# SCH_Test_2024-06-17.net
KiCad netlist of a schematic drawn in EasyEDA
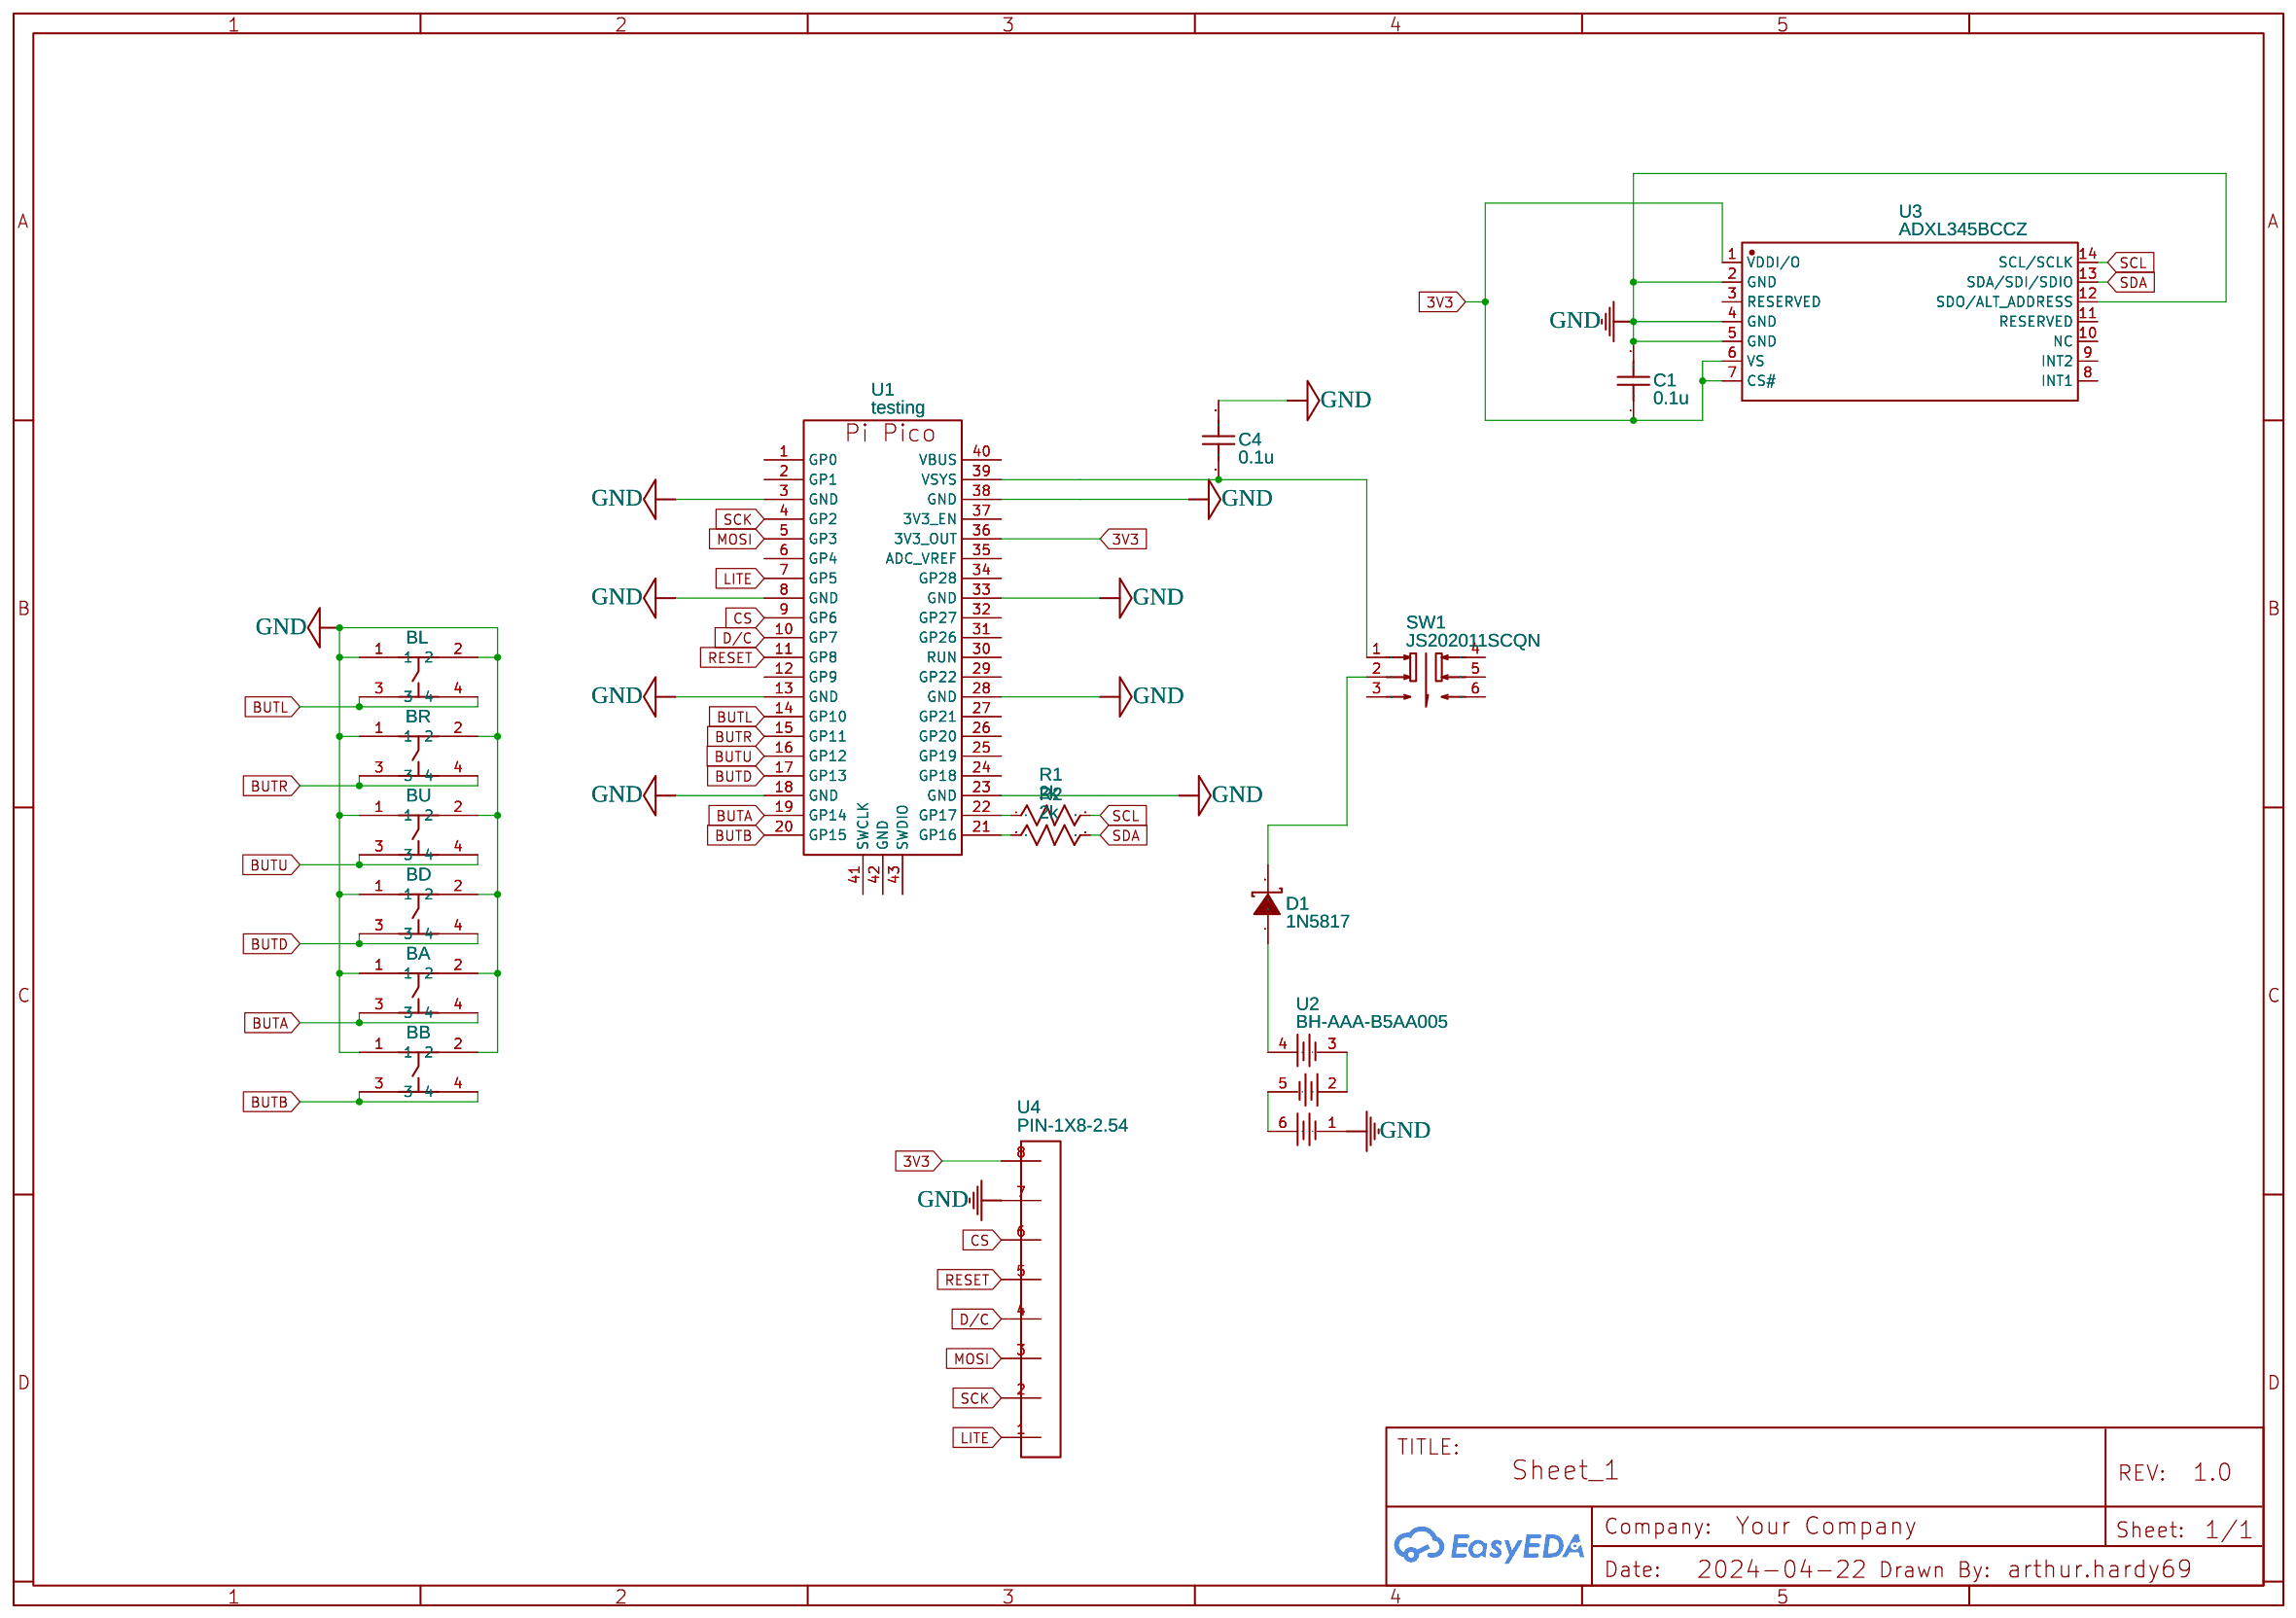
[diagram p0: schematic sheet]

(export (version "E")
  (design (tool "Eeschema 10.0.6"))
  (components
    (comp (ref "BA")
      (value "A")
      (fields (field (name "Manufacturer Part") "3101") (field (name "Manufacturer") "Adafruit"))
      (libsource (lib "") (part "Soft Tactile Button 8x8 (Adafruit 3101)"))
    )
    (comp (ref "BB")
      (value "B")
      (fields (field (name "Manufacturer Part") "3101") (field (name "Manufacturer") "Adafruit"))
      (libsource (lib "") (part "Soft Tactile Button 8x8 (Adafruit 3101)_1"))
    )
    (comp (ref "BD")
      (value "Down")
      (fields (field (name "Manufacturer Part") "3101") (field (name "Manufacturer") "Adafruit"))
      (libsource (lib "") (part "Soft Tactile Button 8x8 (Adafruit 3101)_4"))
    )
    (comp (ref "BL")
      (value "Left")
      (fields (field (name "Manufacturer Part") "3101") (field (name "Manufacturer") "Adafruit"))
      (libsource (lib "") (part "Soft Tactile Button 8x8 (Adafruit 3101)_2"))
    )
    (comp (ref "BR")
      (value "Right")
      (fields (field (name "Manufacturer Part") "3101") (field (name "Manufacturer") "Adafruit"))
      (libsource (lib "") (part "Soft Tactile Button 8x8 (Adafruit 3101)_3"))
    )
    (comp (ref "BU")
      (value "Up")
      (fields (field (name "Manufacturer Part") "3101") (field (name "Manufacturer") "Adafruit"))
      (libsource (lib "") (part "Soft Tactile Button 8x8 (Adafruit 3101)_5"))
    )
    (comp (ref "C1") (value "0.1u") (libsource (lib "") (part "C_0603_US")))
    (comp (ref "C4") (value "0.1u") (libsource (lib "") (part "C_0603_US")))
    (comp (ref "D1")
      (value "1N5817")
      (fields (field (name "Manufacturer") "MDD"))
      (libsource (lib "") (part "1N5817"))
    )
    (comp (ref "R1") (value "2k") (libsource (lib "") (part "R_0603_US")))
    (comp (ref "R2") (value "2k") (libsource (lib "") (part "R_0603_US")))
    (comp (ref "SW1")
      (value "JS202011SCQN")
      (fields (field (name "Manufacturer") "C&K"))
      (libsource (lib "") (part "JS202011SCQN"))
    )
    (comp (ref "U1")
      (value "testing")
      (fields
        (field (name "Manufacturer Part") "Pi Pico")
        (field (name "Manufacturer") "Raspberry Pi Foundation")
      )
      (libsource (lib "") (part "testing"))
    )
    (comp (ref "U2")
      (value "BH-AAA-B5AA005")
      (fields (field (name "Manufacturer") "MYOUNG(美阳)"))
      (libsource (lib "") (part "BH-AAA-B5AA005"))
    )
    (comp (ref "U3")
      (value "ADXL345BCCZ")
      (fields (field (name "Manufacturer") "ADI(亚德诺)"))
      (libsource (lib "") (part "ADXL345BCCZ"))
    )
    (comp (ref "U4") (value "PIN-1X8-2.54") (libsource (lib "") (part "PIN-1X8-2.54")))
  )
  (nets
    (net (code "1") (name "3V3") (class "Default")
      (node (ref "C1") (pin "1") (pinfunction "1_1") (pintype "unspecified"))
      (node (ref "U1") (pin "36") (pinfunction "3V3_OUT_36") (pintype "unspecified"))
      (node (ref "U3") (pin "1") (pinfunction "VDDI/O_1") (pintype "unspecified"))
      (node (ref "U3") (pin "6") (pinfunction "VS_6") (pintype "unspecified"))
      (node (ref "U3") (pin "7") (pinfunction "CS#_7") (pintype "unspecified"))
      (node (ref "U4") (pin "8") (pintype "unspecified"))
    )
    (net (code "2") (name "BUTA") (class "Default")
      (node (ref "BA") (pin "3") (pinfunction "3_3") (pintype "unspecified"))
      (node (ref "BA") (pin "4") (pinfunction "4_4") (pintype "unspecified"))
      (node (ref "U1") (pin "19") (pinfunction "GP14_19") (pintype "unspecified"))
    )
    (net (code "3") (name "BUTB") (class "Default")
      (node (ref "BB") (pin "3") (pinfunction "3_3") (pintype "unspecified"))
      (node (ref "BB") (pin "4") (pinfunction "4_4") (pintype "unspecified"))
      (node (ref "U1") (pin "20") (pinfunction "GP15_20") (pintype "unspecified"))
    )
    (net (code "4") (name "BUTD") (class "Default")
      (node (ref "BD") (pin "3") (pinfunction "3_3") (pintype "unspecified"))
      (node (ref "BD") (pin "4") (pinfunction "4_4") (pintype "unspecified"))
      (node (ref "U1") (pin "17") (pinfunction "GP13_17") (pintype "unspecified"))
    )
    (net (code "5") (name "BUTL") (class "Default")
      (node (ref "BL") (pin "3") (pinfunction "3_3") (pintype "unspecified"))
      (node (ref "BL") (pin "4") (pinfunction "4_4") (pintype "unspecified"))
      (node (ref "U1") (pin "14") (pinfunction "GP10_14") (pintype "unspecified"))
    )
    (net (code "6") (name "BUTR") (class "Default")
      (node (ref "BR") (pin "3") (pinfunction "3_3") (pintype "unspecified"))
      (node (ref "BR") (pin "4") (pinfunction "4_4") (pintype "unspecified"))
      (node (ref "U1") (pin "15") (pinfunction "GP11_15") (pintype "unspecified"))
    )
    (net (code "7") (name "BUTU") (class "Default")
      (node (ref "BU") (pin "3") (pinfunction "3_3") (pintype "unspecified"))
      (node (ref "BU") (pin "4") (pinfunction "4_4") (pintype "unspecified"))
      (node (ref "U1") (pin "16") (pinfunction "GP12_16") (pintype "unspecified"))
    )
    (net (code "8") (name "CS") (class "Default")
      (node (ref "U1") (pin "9") (pinfunction "GP6_9") (pintype "unspecified"))
      (node (ref "U4") (pin "6") (pintype "unspecified"))
    )
    (net (code "9") (name "D{slash}C") (class "Default")
      (node (ref "U1") (pin "10") (pinfunction "GP7_10") (pintype "unspecified"))
      (node (ref "U4") (pin "4") (pintype "unspecified"))
    )
    (net (code "10") (name "GND") (class "Default")
      (node (ref "BA") (pin "1") (pinfunction "1_1") (pintype "unspecified"))
      (node (ref "BA") (pin "2") (pinfunction "2_2") (pintype "unspecified"))
      (node (ref "BB") (pin "1") (pinfunction "1_1") (pintype "unspecified"))
      (node (ref "BB") (pin "2") (pinfunction "2_2") (pintype "unspecified"))
      (node (ref "BD") (pin "1") (pinfunction "1_1") (pintype "unspecified"))
      (node (ref "BD") (pin "2") (pinfunction "2_2") (pintype "unspecified"))
      (node (ref "BL") (pin "1") (pinfunction "1_1") (pintype "unspecified"))
      (node (ref "BL") (pin "2") (pinfunction "2_2") (pintype "unspecified"))
      (node (ref "BR") (pin "1") (pinfunction "1_1") (pintype "unspecified"))
      (node (ref "BR") (pin "2") (pinfunction "2_2") (pintype "unspecified"))
      (node (ref "BU") (pin "1") (pinfunction "1_1") (pintype "unspecified"))
      (node (ref "BU") (pin "2") (pinfunction "2_2") (pintype "unspecified"))
      (node (ref "C1") (pin "2") (pinfunction "2_2") (pintype "unspecified"))
      (node (ref "C4") (pin "2") (pinfunction "2_2") (pintype "unspecified"))
      (node (ref "U1") (pin "13") (pinfunction "GND_13") (pintype "unspecified"))
      (node (ref "U1") (pin "18") (pinfunction "GND_18") (pintype "unspecified"))
      (node (ref "U1") (pin "23") (pinfunction "GND_23") (pintype "unspecified"))
      (node (ref "U1") (pin "28") (pinfunction "GND_28") (pintype "unspecified"))
      (node (ref "U1") (pin "3") (pinfunction "GND_3") (pintype "unspecified"))
      (node (ref "U1") (pin "33") (pinfunction "GND_33") (pintype "unspecified"))
      (node (ref "U1") (pin "38") (pinfunction "GND_38") (pintype "unspecified"))
      (node (ref "U1") (pin "8") (pinfunction "GND_8") (pintype "unspecified"))
      (node (ref "U2") (pin "1") (pinfunction "-_1") (pintype "input"))
      (node (ref "U3") (pin "12") (pinfunction "SDO/ALT_ADDRESS_12") (pintype "unspecified"))
      (node (ref "U3") (pin "2") (pinfunction "GND_2") (pintype "unspecified"))
      (node (ref "U3") (pin "4") (pinfunction "GND_4") (pintype "unspecified"))
      (node (ref "U3") (pin "5") (pinfunction "GND_5") (pintype "unspecified"))
      (node (ref "U4") (pin "7") (pintype "unspecified"))
    )
    (net (code "11") (name "LITE") (class "Default")
      (node (ref "U1") (pin "7") (pinfunction "GP5_7") (pintype "unspecified"))
      (node (ref "U4") (pin "1") (pintype "unspecified"))
    )
    (net (code "12") (name "MOSI") (class "Default")
      (node (ref "U1") (pin "5") (pinfunction "GP3_5") (pintype "unspecified"))
      (node (ref "U4") (pin "3") (pintype "unspecified"))
    )
    (net (code "13") (name "Net-(D1-A)") (class "Default")
      (node (ref "D1") (pin "1") (pinfunction "A_1") (pintype "unspecified"))
      (node (ref "U2") (pin "4") (pinfunction "+_4") (pintype "input"))
    )
    (net (code "14") (name "Net-(D1-K)") (class "Default")
      (node (ref "D1") (pin "2") (pinfunction "K_2") (pintype "unspecified"))
      (node (ref "SW1") (pin "2") (pinfunction "2_2") (pintype "unspecified"))
    )
    (net (code "15") (name "Net-(U1-GP16)") (class "Default")
      (node (ref "R2") (pin "1") (pinfunction "1_1") (pintype "unspecified"))
      (node (ref "U1") (pin "21") (pinfunction "GP16_21") (pintype "unspecified"))
    )
    (net (code "16") (name "Net-(U1-GP17)") (class "Default")
      (node (ref "R1") (pin "1") (pinfunction "1_1") (pintype "unspecified"))
      (node (ref "U1") (pin "22") (pinfunction "GP17_22") (pintype "unspecified"))
    )
    (net (code "17") (name "Net-(U1-VSYS)") (class "Default")
      (node (ref "C4") (pin "1") (pinfunction "1_1") (pintype "unspecified"))
      (node (ref "SW1") (pin "1") (pinfunction "1_1") (pintype "unspecified"))
      (node (ref "U1") (pin "39") (pinfunction "VSYS_39") (pintype "unspecified"))
    )
    (net (code "18") (name "Net-(U2-+-Pad2)") (class "Default")
      (node (ref "U2") (pin "2") (pinfunction "+_2") (pintype "input"))
      (node (ref "U2") (pin "3") (pinfunction "-_3") (pintype "input"))
    )
    (net (code "19") (name "Net-(U2-+-Pad6)") (class "Default")
      (node (ref "U2") (pin "5") (pinfunction "-_5") (pintype "input"))
      (node (ref "U2") (pin "6") (pinfunction "+_6") (pintype "input"))
    )
    (net (code "20") (name "RESET") (class "Default")
      (node (ref "U1") (pin "11") (pinfunction "GP8_11") (pintype "unspecified"))
      (node (ref "U4") (pin "5") (pintype "unspecified"))
    )
    (net (code "21") (name "SCK") (class "Default")
      (node (ref "U1") (pin "4") (pinfunction "GP2_4") (pintype "unspecified"))
      (node (ref "U4") (pin "2") (pintype "unspecified"))
    )
    (net (code "22") (name "SCL") (class "Default")
      (node (ref "R1") (pin "2") (pinfunction "2_2") (pintype "unspecified"))
      (node (ref "U3") (pin "14") (pinfunction "SCL/SCLK_14") (pintype "unspecified"))
    )
    (net (code "23") (name "SDA") (class "Default")
      (node (ref "R2") (pin "2") (pinfunction "2_2") (pintype "unspecified"))
      (node (ref "U3") (pin "13") (pinfunction "SDA/SDI/SDIO_13") (pintype "unspecified"))
    )
    (net (code "24") (name "unconnected-(SW1-Pad3)") (class "Default")
      (node (ref "SW1") (pin "3") (pinfunction "3_3") (pintype "unspecified"))
    )
    (net (code "25") (name "unconnected-(SW1-Pad4)") (class "Default")
      (node (ref "SW1") (pin "4") (pinfunction "4_4") (pintype "unspecified"))
    )
    (net (code "26") (name "unconnected-(SW1-Pad5)") (class "Default")
      (node (ref "SW1") (pin "5") (pinfunction "5_5") (pintype "unspecified"))
    )
    (net (code "27") (name "unconnected-(SW1-Pad6)") (class "Default")
      (node (ref "SW1") (pin "6") (pinfunction "6_6") (pintype "unspecified"))
    )
    (net (code "28") (name "unconnected-(U1-3V3_EN-Pad37)") (class "Default")
      (node (ref "U1") (pin "37") (pinfunction "3V3_EN_37") (pintype "unspecified"))
    )
    (net (code "29") (name "unconnected-(U1-ADC_VREF-Pad35)") (class "Default")
      (node (ref "U1") (pin "35") (pinfunction "ADC_VREF_35") (pintype "unspecified"))
    )
    (net (code "30") (name "unconnected-(U1-GND-Pad42)") (class "Default")
      (node (ref "U1") (pin "42") (pinfunction "GND_42") (pintype "unspecified"))
    )
    (net (code "31") (name "unconnected-(U1-GP0-Pad1)") (class "Default")
      (node (ref "U1") (pin "1") (pinfunction "GP0_1") (pintype "unspecified"))
    )
    (net (code "32") (name "unconnected-(U1-GP1-Pad2)") (class "Default")
      (node (ref "U1") (pin "2") (pinfunction "GP1_2") (pintype "unspecified"))
    )
    (net (code "33") (name "unconnected-(U1-GP4-Pad6)") (class "Default")
      (node (ref "U1") (pin "6") (pinfunction "GP4_6") (pintype "unspecified"))
    )
    (net (code "34") (name "unconnected-(U1-GP9-Pad12)") (class "Default")
      (node (ref "U1") (pin "12") (pinfunction "GP9_12") (pintype "unspecified"))
    )
    (net (code "35") (name "unconnected-(U1-GP18-Pad24)") (class "Default")
      (node (ref "U1") (pin "24") (pinfunction "GP18_24") (pintype "unspecified"))
    )
    (net (code "36") (name "unconnected-(U1-GP19-Pad25)") (class "Default")
      (node (ref "U1") (pin "25") (pinfunction "GP19_25") (pintype "unspecified"))
    )
    (net (code "37") (name "unconnected-(U1-GP20-Pad26)") (class "Default")
      (node (ref "U1") (pin "26") (pinfunction "GP20_26") (pintype "unspecified"))
    )
    (net (code "38") (name "unconnected-(U1-GP21-Pad27)") (class "Default")
      (node (ref "U1") (pin "27") (pinfunction "GP21_27") (pintype "unspecified"))
    )
    (net (code "39") (name "unconnected-(U1-GP22-Pad29)") (class "Default")
      (node (ref "U1") (pin "29") (pinfunction "GP22_29") (pintype "unspecified"))
    )
    (net (code "40") (name "unconnected-(U1-GP26-Pad31)") (class "Default")
      (node (ref "U1") (pin "31") (pinfunction "GP26_31") (pintype "unspecified"))
    )
    (net (code "41") (name "unconnected-(U1-GP27-Pad32)") (class "Default")
      (node (ref "U1") (pin "32") (pinfunction "GP27_32") (pintype "unspecified"))
    )
    (net (code "42") (name "unconnected-(U1-GP28-Pad34)") (class "Default")
      (node (ref "U1") (pin "34") (pinfunction "GP28_34") (pintype "unspecified"))
    )
    (net (code "43") (name "unconnected-(U1-RUN-Pad30)") (class "Default")
      (node (ref "U1") (pin "30") (pinfunction "RUN_30") (pintype "unspecified"))
    )
    (net (code "44") (name "unconnected-(U1-SWCLK-Pad41)") (class "Default")
      (node (ref "U1") (pin "41") (pinfunction "SWCLK_41") (pintype "unspecified"))
    )
    (net (code "45") (name "unconnected-(U1-SWDIO-Pad43)") (class "Default")
      (node (ref "U1") (pin "43") (pinfunction "SWDIO_43") (pintype "unspecified"))
    )
    (net (code "46") (name "unconnected-(U1-VBUS-Pad40)") (class "Default")
      (node (ref "U1") (pin "40") (pinfunction "VBUS_40") (pintype "unspecified"))
    )
    (net (code "47") (name "unconnected-(U3-INT1-Pad8)") (class "Default")
      (node (ref "U3") (pin "8") (pinfunction "INT1_8") (pintype "unspecified"))
    )
    (net (code "48") (name "unconnected-(U3-INT2-Pad9)") (class "Default")
      (node (ref "U3") (pin "9") (pinfunction "INT2_9") (pintype "unspecified"))
    )
    (net (code "49") (name "unconnected-(U3-NC-Pad10)") (class "Default")
      (node (ref "U3") (pin "10") (pinfunction "NC_10") (pintype "unspecified"))
    )
    (net (code "50") (name "unconnected-(U3-RESERVED-Pad3)") (class "Default")
      (node (ref "U3") (pin "3") (pinfunction "RESERVED_3") (pintype "unspecified"))
    )
    (net (code "51") (name "unconnected-(U3-RESERVED-Pad11)") (class "Default")
      (node (ref "U3") (pin "11") (pinfunction "RESERVED_11") (pintype "unspecified"))
    )
  )
)
